# Power_Regulators_RF_2.net
KiCad netlist of a schematic drawn in Altium Designer
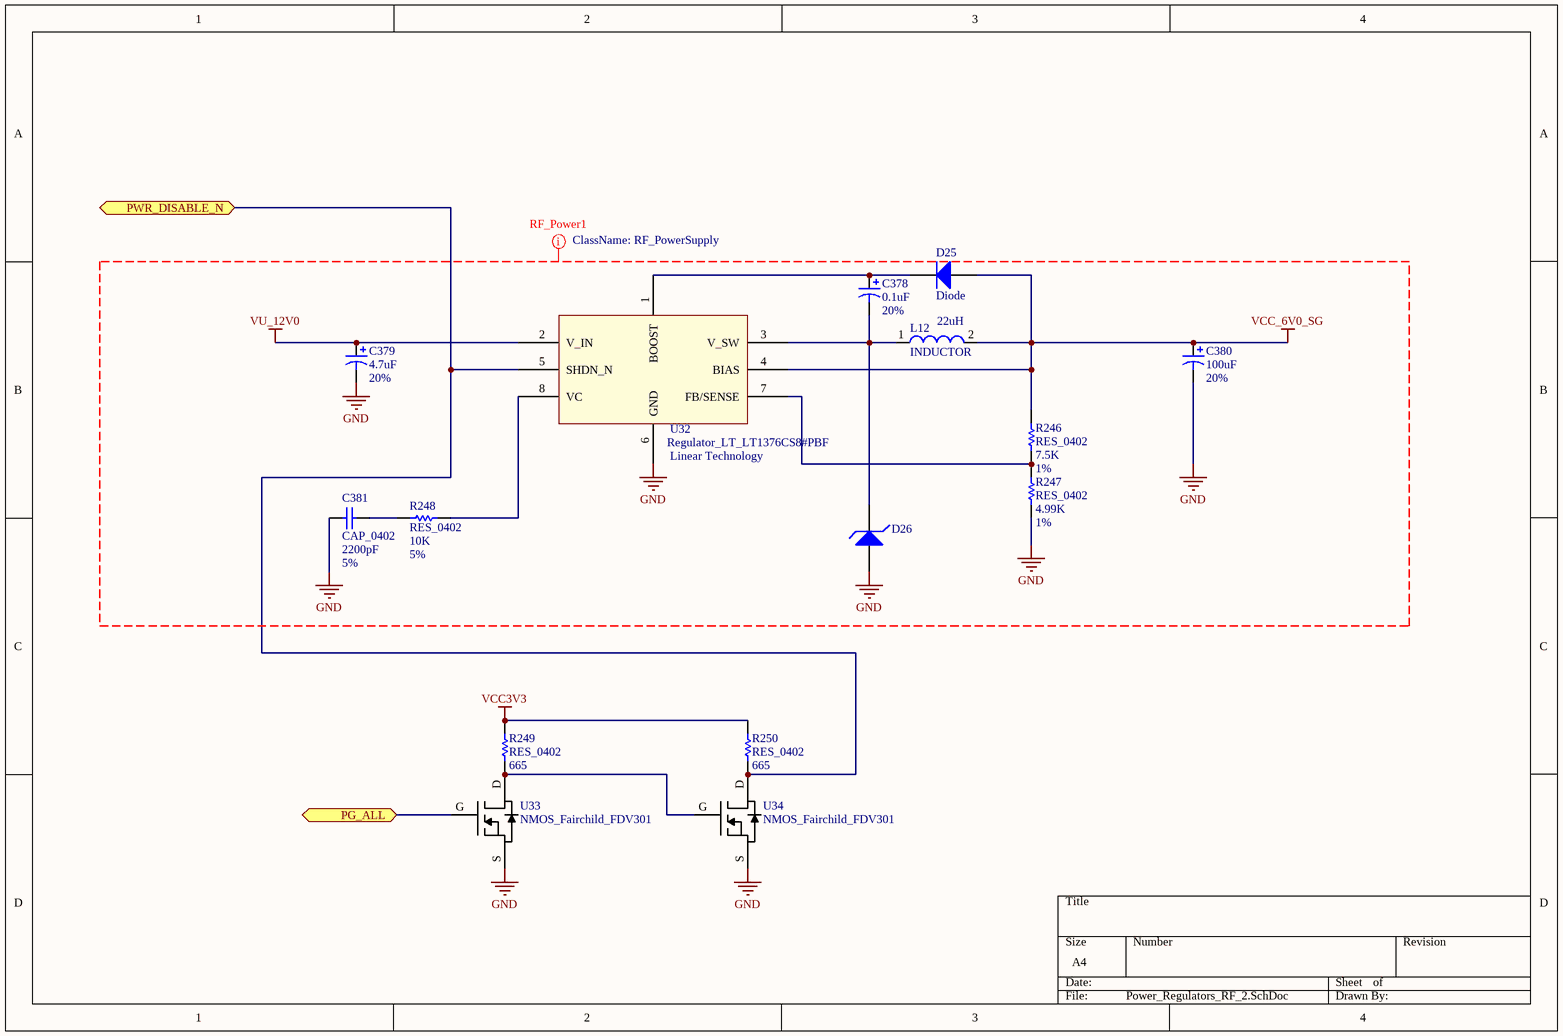
[diagram p0: Power_Regulators_RF_2.SchDoc]

(export (version "E")
  (design (tool "Eeschema 10.0.6"))
  (components
    (comp (ref "C378")
      (value "0.1uF")
      (footprint "Polarized_CAPC1206(3216)")
      (description "CAP TANT 0.1UF 35V 20% 1206")
      (fields
        (field (name "TOLERANCE") "20%")
        (field (name "PART NUMBER") "T491A104M035AT")
        (field (name "MANUFACTURER") "Kemet")
      )
      (libsource (lib "COMRAD_Database") (part "Cap Pol1"))
    )
    (comp (ref "C379")
      (value "4.7uF")
      (footprint "Polarized_CAPC1206(3216)")
      (description "CAP TANT 4.7UF 25V 20% 1206")
      (fields
        (field (name "TOLERANCE") "20%")
        (field (name "PART NUMBER") "T491A475M025AT")
        (field (name "MANUFACTURER") "Kemet")
      )
      (libsource (lib "COMRAD_Database") (part "Cap Pol1"))
    )
    (comp (ref "C380")
      (value "100uF")
      (footprint "Polarized_CAPC1210(3225)")
      (description "100uF, tantalum, 20% 10V, 1210")
      (fields
        (field (name "TOLERANCE") "20%")
        (field (name "PART NUMBER") "TLCT107M010XTA")
        (field (name "MANUFACTURER") "AVX Corporation")
      )
      (libsource (lib "COMRAD_Database") (part "Cap Pol1"))
    )
    (comp (ref "C381")
      (value "CAP_0402")
      (footprint "CAPC0402(1005)60_N")
      (description "CAP CER 2200PF 10V 5% SL 0402")
      (fields
        (field (name "ALTIUM_VALUE") "2200pF")
        (field (name "TOLERANCE") "5%")
        (field (name "PART NUMBER") "C1005SL1A222J")
        (field (name "MANUFACTURER") "TDK Corporation")
      )
      (libsource (lib "COMRAD_Database") (part "CAP_0402"))
    )
    (comp (ref "D25")
      (value "Diode")
      (footprint "Diode_DB2J31700L_2-PIN")
      (description "DIODE 30V 1A SMINI2")
      (fields
        (field (name "PART NUMBER") "DB2J31700L")
        (field (name "MANUFACTURER") "Panasonic Electronic Components - Semiconductor Products")
      )
      (libsource (lib "COMRAD_Database") (part "Diode"))
    )
    (comp (ref "D26")
      (value "Shottky Diode")
      (footprint "SchottkyDiode_SS2P2-M384A_2-PIN")
      (description "DIODE SCHOTTKY 2A 20V SMP")
      (fields
        (field (name "PART NUMBER") "SS2P2-M3/84A")
        (field (name "MANUFACTURER") "Vishay Semiconductor Diodes Division")
      )
      (libsource (lib "COMRAD_Database") (part "ShottkyDiode"))
    )
    (comp (ref "L12")
      (value "INDUCTOR")
      (footprint "Inductor_IHSM4825ER_2-PIN")
      (description "Surface Mount Inductor,22uH,1.7A")
      (fields
        (field (name "ALTIUM_VALUE") "22uH")
        (field (name "PART NUMBER") "IHSM4825ER2R0L")
        (field (name "MANUFACTURER") "Vishay Dale")
      )
      (libsource (lib "COMRAD_Database") (part "INDUCTOR"))
    )
    (comp (ref "R246")
      (value "RES_0402")
      (footprint "RESC0402(1005)_N")
      (description "RES 7.50K OHM 1/10W 1% 0402 SMD")
      (fields
        (field (name "ALTIUM_VALUE") "7.5K")
        (field (name "TOLERANCE") "1%")
        (field (name "PART NUMBER") "ERJ-2RKF7501X")
        (field (name "MANUFACTURER") "Panasonic Electronic Components")
      )
      (libsource (lib "COMRAD_Database") (part "RES_0402"))
    )
    (comp (ref "R247")
      (value "RES_0402")
      (footprint "RESC0402(1005)_N")
      (description "4.99K ohm, 1% 1/16W, 0402")
      (fields
        (field (name "ALTIUM_VALUE") "4.99K")
        (field (name "TOLERANCE") "1%")
        (field (name "PART NUMBER") "CRCW04024K99FKED")
        (field (name "MANUFACTURER") "Vishay/Dale")
      )
      (libsource (lib "COMRAD_Database") (part "RES_0402"))
    )
    (comp (ref "R248")
      (value "RES_0402")
      (footprint "RESC0402(1005)_N")
      (description "10K ohm, 5%, 1/16W, 0402")
      (fields
        (field (name "ALTIUM_VALUE") "10K")
        (field (name "TOLERANCE") "5%")
        (field (name "PART NUMBER") "RC0402JR-0710KL")
        (field (name "MANUFACTURER") "Yageo America")
      )
      (libsource (lib "COMRAD_Database") (part "RES_0402"))
    )
    (comp (ref "R249")
      (value "RES_0402")
      (footprint "RESC0402(1005)_N")
      (description "RES 665 OHM 1/10W 1% 0402 SMD")
      (fields
        (field (name "ALTIUM_VALUE") "665")
        (field (name "PART NUMBER") "ERJ-2RKF6650X")
        (field (name "MANUFACTURER") "Panasonic Electronic Components")
      )
      (libsource (lib "COMRAD_Database") (part "RES_0402"))
    )
    (comp (ref "R250")
      (value "RES_0402")
      (footprint "RESC0402(1005)_N")
      (description "RES 665 OHM 1/10W 1% 0402 SMD")
      (fields
        (field (name "ALTIUM_VALUE") "665")
        (field (name "PART NUMBER") "ERJ-2RKF6650X")
        (field (name "MANUFACTURER") "Panasonic Electronic Components")
      )
      (libsource (lib "COMRAD_Database") (part "RES_0402"))
    )
    (comp (ref "U32")
      (value "Regulator_LT_LT1376CS8#PBF")
      (footprint "LT1376CS8#PBF_8SOIC")
      (description "IC REG BUCK ADJ 1.5A 8SOIC")
      (fields (field (name "PART NUMBER") "LT1376CS8#PBF") (field (name "MANUFACTURER") "Linear Technology"))
      (libsource (lib "COMRAD_Database") (part "Regulator_LT_LT1376CS8#PBF"))
    )
    (comp (ref "U33")
      (value "NMOS_Fairchild_FDV301")
      (footprint "NMOS_Fairchild_FDV301_SOT23-3")
      (description "MOSFET N-CH 25V 220MA SOT-23")
      (fields (field (name "PART NUMBER") "FDV301N") (field (name "MANUFACTURER") "Fairchild Semiconductor"))
      (libsource (lib "COMRAD_Database") (part "NMOS_Fairchild_FDV301"))
    )
    (comp (ref "U34")
      (value "NMOS_Fairchild_FDV301")
      (footprint "NMOS_Fairchild_FDV301_SOT23-3")
      (description "MOSFET N-CH 25V 220MA SOT-23")
      (fields (field (name "PART NUMBER") "FDV301N") (field (name "MANUFACTURER") "Fairchild Semiconductor"))
      (libsource (lib "COMRAD_Database") (part "NMOS_Fairchild_FDV301"))
    )
  )
  (nets
    (net (code "1") (name "/PG_ALL") (class "Default") (node (ref "U33") (pin "G") (pintype "passive")))
    (net (code "2") (name "/PWR_DISABLE_N") (class "Default")
      (node (ref "R250") (pin "1") (pinfunction "1_1") (pintype "passive"))
      (node (ref "U32") (pin "5") (pinfunction "SHDN_N_5") (pintype "passive"))
      (node (ref "U34") (pin "D") (pintype "passive"))
    )
    (net (code "3") (name "GND") (class "Default")
      (node (ref "C379") (pin "2") (pinfunction "2_2") (pintype "passive"))
      (node (ref "C380") (pin "2") (pinfunction "2_2") (pintype "passive"))
      (node (ref "C381") (pin "1") (pinfunction "1_1") (pintype "passive"))
      (node (ref "D26") (pin "2") (pinfunction "A_2") (pintype "passive"))
      (node (ref "R247") (pin "1") (pinfunction "1_1") (pintype "passive"))
      (node (ref "U32") (pin "6") (pinfunction "GND_6") (pintype "power_in"))
      (node (ref "U33") (pin "S") (pintype "passive"))
      (node (ref "U34") (pin "S") (pintype "passive"))
    )
    (net (code "4") (name "Net-(C381-Pad2)") (class "Default")
      (node (ref "C381") (pin "2") (pinfunction "2_2") (pintype "passive"))
      (node (ref "R248") (pin "1") (pinfunction "1_1") (pintype "passive"))
    )
    (net (code "5") (name "Net-(D25-K)") (class "Default")
      (node (ref "C378") (pin "1") (pinfunction "1_1") (pintype "passive"))
      (node (ref "D25") (pin "1") (pinfunction "K_1") (pintype "passive"))
      (node (ref "U32") (pin "1") (pinfunction "BOOST_1") (pintype "passive"))
    )
    (net (code "6") (name "Net-(D26-K)") (class "Default")
      (node (ref "C378") (pin "2") (pinfunction "2_2") (pintype "passive"))
      (node (ref "D26") (pin "1") (pinfunction "K_1") (pintype "passive"))
      (node (ref "L12") (pin "1") (pinfunction "1_1") (pintype "passive"))
      (node (ref "U32") (pin "3") (pinfunction "V_SW_3") (pintype "power_in"))
    )
    (net (code "7") (name "Net-(R249-Pad1)") (class "Default")
      (node (ref "R249") (pin "1") (pinfunction "1_1") (pintype "passive"))
      (node (ref "U33") (pin "D") (pintype "passive"))
      (node (ref "U34") (pin "G") (pintype "passive"))
    )
    (net (code "8") (name "Net-(U32-FB{slash}SENSE)") (class "Default")
      (node (ref "R246") (pin "1") (pinfunction "1_1") (pintype "passive"))
      (node (ref "R247") (pin "2") (pinfunction "2_2") (pintype "passive"))
      (node (ref "U32") (pin "7") (pinfunction "FB/SENSE_7") (pintype "power_in"))
    )
    (net (code "9") (name "Net-(U32-VC)") (class "Default")
      (node (ref "R248") (pin "2") (pinfunction "2_2") (pintype "passive"))
      (node (ref "U32") (pin "8") (pinfunction "VC_8") (pintype "passive"))
    )
    (net (code "10") (name "VCC3V3") (class "Default")
      (node (ref "R249") (pin "2") (pinfunction "2_2") (pintype "passive"))
      (node (ref "R250") (pin "2") (pinfunction "2_2") (pintype "passive"))
    )
    (net (code "11") (name "VCC_6V0_SG") (class "Default")
      (node (ref "C380") (pin "1") (pinfunction "1_1") (pintype "passive"))
      (node (ref "D25") (pin "2") (pinfunction "A_2") (pintype "passive"))
      (node (ref "L12") (pin "2") (pinfunction "2_2") (pintype "passive"))
      (node (ref "R246") (pin "2") (pinfunction "2_2") (pintype "passive"))
      (node (ref "U32") (pin "4") (pinfunction "BIAS_4") (pintype "passive"))
    )
    (net (code "12") (name "VU_12V0") (class "Default")
      (node (ref "C379") (pin "1") (pinfunction "1_1") (pintype "passive"))
      (node (ref "U32") (pin "2") (pinfunction "V_IN_2") (pintype "power_in"))
    )
  )
)
